# BalancingPassiveComponents.net
KiCad netlist of a schematic drawn in Altium Designer
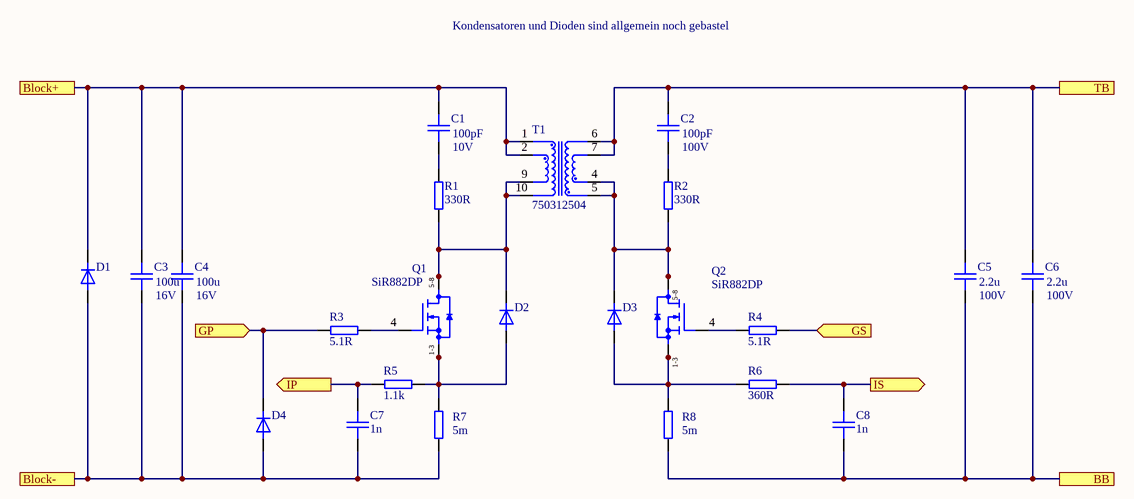
[diagram p0: BalancingPassiveComponents.SchDoc]

(export (version "E")
  (design (tool "Eeschema 10.0.6"))
  (components
    (comp (ref "C1")
      (value "100pF")
      (footprint "CAP 0603")
      (fields (field (name "VOLTAGE") "10V"))
      (libsource (lib "SVNDatabase") (part "Capacitor"))
    )
    (comp (ref "C2")
      (value "100pF")
      (footprint "CAP 0603")
      (fields (field (name "VOLTAGE") "100V"))
      (libsource (lib "SVNDatabase") (part "Capacitor"))
    )
    (comp (ref "C3")
      (value "100u")
      (footprint "CAP 0805")
      (fields (field (name "VOLTAGE") "16V"))
      (libsource (lib "SVNDatabase") (part "Capacitor"))
    )
    (comp (ref "C4")
      (value "100u")
      (footprint "CAP 0805")
      (fields (field (name "VOLTAGE") "16V"))
      (libsource (lib "SVNDatabase") (part "Capacitor"))
    )
    (comp (ref "C5")
      (value "2.2u")
      (footprint "CAP 0805")
      (fields (field (name "VOLTAGE") "100V"))
      (libsource (lib "SVNDatabase") (part "Capacitor"))
    )
    (comp (ref "C6")
      (value "2.2u")
      (footprint "CAP 0805")
      (fields (field (name "VOLTAGE") "100V"))
      (libsource (lib "SVNDatabase") (part "Capacitor"))
    )
    (comp (ref "C7") (value "1n") (footprint "CAP 0603") (libsource (lib "SVNDatabase") (part "Capacitor")))
    (comp (ref "C8") (value "1n") (footprint "CAP 0603") (libsource (lib "SVNDatabase") (part "Capacitor")))
    (comp (ref "D1") (value "~") (footprint "SOD-123") (libsource (lib "SVNDatabase") (part "Diode")))
    (comp (ref "D2") (value "~") (footprint "SOD-123") (libsource (lib "SVNDatabase") (part "Diode")))
    (comp (ref "D3") (value "~") (footprint "SOD-123") (libsource (lib "SVNDatabase") (part "Diode")))
    (comp (ref "D4") (value "~") (footprint "SOD-123") (libsource (lib "SVNDatabase") (part "Diode")))
    (comp (ref "Q1")
      (value "SiR882DP")
      (footprint "PowerPAK SO-8 Single")
      (libsource (lib "SVNDatabase") (part "MOSFET N-Type PowerPAK SO-8"))
    )
    (comp (ref "Q2")
      (value "SiR882DP")
      (footprint "PowerPAK SO-8 Single")
      (libsource (lib "SVNDatabase") (part "MOSFET N-Type PowerPAK SO-8"))
    )
    (comp (ref "R1")
      (value "330R")
      (footprint "0603")
      (fields (field (name "TOLERANCE") "1%"))
      (libsource (lib "SVNDatabase") (part "R"))
    )
    (comp (ref "R2")
      (value "330R")
      (footprint "0603")
      (fields (field (name "TOLERANCE") "1%"))
      (libsource (lib "SVNDatabase") (part "R"))
    )
    (comp (ref "R3")
      (value "5.1R")
      (footprint "0603")
      (fields (field (name "TOLERANCE") "1%"))
      (libsource (lib "SVNDatabase") (part "R"))
    )
    (comp (ref "R4")
      (value "5.1R")
      (footprint "0603")
      (fields (field (name "TOLERANCE") "1%"))
      (libsource (lib "SVNDatabase") (part "R"))
    )
    (comp (ref "R5")
      (value "1.1k")
      (footprint "0603")
      (fields (field (name "TOLERANCE") "1%"))
      (libsource (lib "SVNDatabase") (part "R"))
    )
    (comp (ref "R6")
      (value "360R")
      (footprint "0603")
      (fields (field (name "TOLERANCE") "1%"))
      (libsource (lib "SVNDatabase") (part "R"))
    )
    (comp (ref "R7") (value "5m") (footprint "1210") (libsource (lib "SVNDatabase") (part "R")))
    (comp (ref "R8") (value "5m") (footprint "1210") (libsource (lib "SVNDatabase") (part "R")))
    (comp (ref "T1")
      (value "750312504")
      (footprint "750312504")
      (description "Flyback Transformer")
      (fields (field (name "TOLERANCE") "10%"))
      (libsource (lib "SVNDatabase") (part "750312504"))
    )
  )
  (nets
    (net (code "1") (name "/BB") (class "Default")
      (node (ref "C5") (pin "1") (pinfunction "1_1") (pintype "passive"))
      (node (ref "C6") (pin "1") (pinfunction "1_1") (pintype "passive"))
      (node (ref "C8") (pin "1") (pinfunction "1_1") (pintype "passive"))
      (node (ref "R8") (pin "1") (pinfunction "1_1") (pintype "passive"))
    )
    (net (code "2") (name "/Block+") (class "Default")
      (node (ref "C1") (pin "2") (pinfunction "2_2") (pintype "passive"))
      (node (ref "C3") (pin "2") (pinfunction "2_2") (pintype "passive"))
      (node (ref "C4") (pin "2") (pinfunction "2_2") (pintype "passive"))
      (node (ref "D1") (pin "2") (pinfunction "2_2") (pintype "passive"))
      (node (ref "T1") (pin "1") (pinfunction "1_1") (pintype "passive"))
      (node (ref "T1") (pin "2") (pinfunction "2_2") (pintype "passive"))
    )
    (net (code "3") (name "/Block-") (class "Default")
      (node (ref "C3") (pin "1") (pinfunction "1_1") (pintype "passive"))
      (node (ref "C4") (pin "1") (pinfunction "1_1") (pintype "passive"))
      (node (ref "C7") (pin "1") (pinfunction "1_1") (pintype "passive"))
      (node (ref "D1") (pin "1") (pinfunction "1_1") (pintype "passive"))
      (node (ref "D4") (pin "1") (pinfunction "1_1") (pintype "passive"))
      (node (ref "R7") (pin "1") (pinfunction "1_1") (pintype "passive"))
    )
    (net (code "4") (name "/GP") (class "Default")
      (node (ref "D4") (pin "2") (pinfunction "2_2") (pintype "passive"))
      (node (ref "R3") (pin "1") (pinfunction "1_1") (pintype "passive"))
    )
    (net (code "5") (name "/GS") (class "Default")
      (node (ref "R4") (pin "2") (pinfunction "2_2") (pintype "passive"))
    )
    (net (code "6") (name "/IP") (class "Default")
      (node (ref "C7") (pin "2") (pinfunction "2_2") (pintype "passive"))
      (node (ref "R5") (pin "1") (pinfunction "1_1") (pintype "passive"))
    )
    (net (code "7") (name "/IS") (class "Default")
      (node (ref "C8") (pin "2") (pinfunction "2_2") (pintype "passive"))
      (node (ref "R6") (pin "2") (pinfunction "2_2") (pintype "passive"))
    )
    (net (code "8") (name "/TB") (class "Default")
      (node (ref "C2") (pin "2") (pinfunction "2_2") (pintype "passive"))
      (node (ref "C5") (pin "2") (pinfunction "2_2") (pintype "passive"))
      (node (ref "C6") (pin "2") (pinfunction "2_2") (pintype "passive"))
      (node (ref "T1") (pin "6") (pinfunction "6_6") (pintype "passive"))
      (node (ref "T1") (pin "7") (pinfunction "7_7") (pintype "passive"))
    )
    (net (code "9") (name "Net-(C1-Pad1)") (class "Default")
      (node (ref "C1") (pin "1") (pinfunction "1_1") (pintype "passive"))
      (node (ref "R1") (pin "2") (pinfunction "2_2") (pintype "passive"))
    )
    (net (code "10") (name "Net-(C2-Pad1)") (class "Default")
      (node (ref "C2") (pin "1") (pinfunction "1_1") (pintype "passive"))
      (node (ref "R2") (pin "2") (pinfunction "2_2") (pintype "passive"))
    )
    (net (code "11") (name "Net-(D2-Pad1)") (class "Default")
      (node (ref "D2") (pin "1") (pinfunction "1_1") (pintype "passive"))
      (node (ref "Q1") (pin "1") (pinfunction "S_1") (pintype "passive"))
      (node (ref "Q1") (pin "2") (pinfunction "S_2") (pintype "passive"))
      (node (ref "Q1") (pin "3") (pinfunction "S_3") (pintype "passive"))
      (node (ref "R5") (pin "2") (pinfunction "2_2") (pintype "passive"))
      (node (ref "R7") (pin "2") (pinfunction "2_2") (pintype "passive"))
    )
    (net (code "12") (name "Net-(D2-Pad2)") (class "Default")
      (node (ref "D2") (pin "2") (pinfunction "2_2") (pintype "passive"))
      (node (ref "Q1") (pin "5") (pinfunction "D_5") (pintype "passive"))
      (node (ref "Q1") (pin "6") (pinfunction "D_6") (pintype "passive"))
      (node (ref "Q1") (pin "7") (pinfunction "D_7") (pintype "passive"))
      (node (ref "Q1") (pin "8") (pinfunction "D_8") (pintype "passive"))
      (node (ref "R1") (pin "1") (pinfunction "1_1") (pintype "passive"))
      (node (ref "T1") (pin "10") (pinfunction "10_10") (pintype "passive"))
      (node (ref "T1") (pin "9") (pinfunction "9_9") (pintype "passive"))
    )
    (net (code "13") (name "Net-(D3-Pad1)") (class "Default")
      (node (ref "D3") (pin "1") (pinfunction "1_1") (pintype "passive"))
      (node (ref "Q2") (pin "1") (pinfunction "S_1") (pintype "passive"))
      (node (ref "Q2") (pin "2") (pinfunction "S_2") (pintype "passive"))
      (node (ref "Q2") (pin "3") (pinfunction "S_3") (pintype "passive"))
      (node (ref "R6") (pin "1") (pinfunction "1_1") (pintype "passive"))
      (node (ref "R8") (pin "2") (pinfunction "2_2") (pintype "passive"))
    )
    (net (code "14") (name "Net-(D3-Pad2)") (class "Default")
      (node (ref "D3") (pin "2") (pinfunction "2_2") (pintype "passive"))
      (node (ref "Q2") (pin "5") (pinfunction "D_5") (pintype "passive"))
      (node (ref "Q2") (pin "6") (pinfunction "D_6") (pintype "passive"))
      (node (ref "Q2") (pin "7") (pinfunction "D_7") (pintype "passive"))
      (node (ref "Q2") (pin "8") (pinfunction "D_8") (pintype "passive"))
      (node (ref "R2") (pin "1") (pinfunction "1_1") (pintype "passive"))
      (node (ref "T1") (pin "4") (pinfunction "4_4") (pintype "passive"))
      (node (ref "T1") (pin "5") (pinfunction "5_5") (pintype "passive"))
    )
    (net (code "15") (name "Net-(Q1-G)") (class "Default")
      (node (ref "Q1") (pin "4") (pinfunction "G_4") (pintype "passive"))
      (node (ref "R3") (pin "2") (pinfunction "2_2") (pintype "passive"))
    )
    (net (code "16") (name "Net-(Q2-G)") (class "Default")
      (node (ref "Q2") (pin "4") (pinfunction "G_4") (pintype "passive"))
      (node (ref "R4") (pin "1") (pinfunction "1_1") (pintype "passive"))
    )
  )
)
